# BatteryCharger.net
KiCad netlist of a schematic drawn in Altium Designer
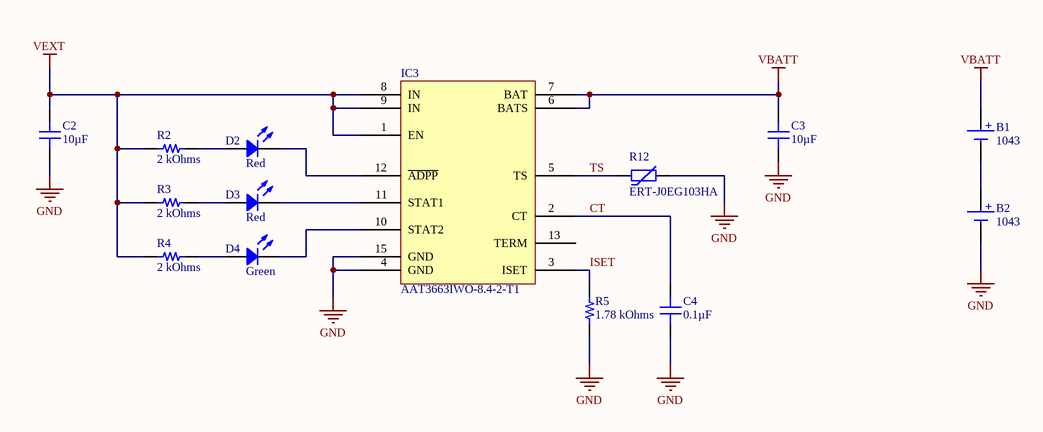
[diagram p0: BatteryCharger.SchDoc]

(export (version "E")
  (design (tool "Eeschema 10.0.6"))
  (components
    (comp (ref "B1")
      (value "1043")
      (footprint "KEYSTONE 1043")
      (description "BATTERY HOLDER 18650 PC PIN")
      (fields (field (name "MANUFACTURER") "Keystone Electronics"))
      (libsource (lib "Celestial Altium Library - altium_library") (part "Keystone 1043"))
    )
    (comp (ref "B2")
      (value "1043")
      (footprint "KEYSTONE 1043")
      (description "BATTERY HOLDER 18650 PC PIN")
      (fields (field (name "MANUFACTURER") "Keystone Electronics"))
      (libsource (lib "Celestial Altium Library - altium_library") (part "Keystone 1043"))
    )
    (comp (ref "C2")
      (value "10µF")
      (footprint "CAP 1206_3216 - 1.8MM")
      (description "CAP CER 10UF 10V X5R 1206")
      (fields
        (field (name "PART NUMBER") "CL31A106KPHNNNE")
        (field (name "MANUFACTURER") "Samsung Electro-Mechanics")
      )
      (libsource (lib "Celestial Altium Library - altium_library") (part "Capacitor"))
    )
    (comp (ref "C3")
      (value "10µF")
      (footprint "CAP 1206_3216 - 1.8MM")
      (description "CAP CER 10UF 10V X5R 1206")
      (fields
        (field (name "PART NUMBER") "CL31A106KPHNNNE")
        (field (name "MANUFACTURER") "Samsung Electro-Mechanics")
      )
      (libsource (lib "Celestial Altium Library - altium_library") (part "Capacitor"))
    )
    (comp (ref "C4")
      (value "0.1µF")
      (footprint "CAP 0603_1608")
      (description "CAP CER 0.1UF 25V Y5V 0603")
      (fields (field (name "PART NUMBER") "CC0603MRY5V8BB104") (field (name "MANUFACTURER") "Yageo"))
      (libsource (lib "Celestial Altium Library - altium_library") (part "Capacitor"))
    )
    (comp (ref "D2")
      (value "Red")
      (footprint "LED 0603_1608 RED")
      (description "LED RED CLEAR 2SMD")
      (fields
        (field (name "PART NUMBER") "19-213USRC/S259/TR8")
        (field (name "MANUFACTURER") "Everlight Electronics Co Ltd")
      )
      (libsource (lib "Celestial Altium Library - altium_library") (part "LED"))
    )
    (comp (ref "D3")
      (value "Red")
      (footprint "LED 0603_1608 RED")
      (description "LED RED CLEAR 2SMD")
      (fields
        (field (name "PART NUMBER") "19-213USRC/S259/TR8")
        (field (name "MANUFACTURER") "Everlight Electronics Co Ltd")
      )
      (libsource (lib "Celestial Altium Library - altium_library") (part "LED"))
    )
    (comp (ref "D4")
      (value "Green")
      (footprint "LED 0603_1608 GREEN")
      (description "LED GREEN CLEAR CHIP SMD")
      (fields (field (name "PART NUMBER") "LTST-C190KGKT") (field (name "MANUFACTURER") "Lite-On Inc."))
      (libsource (lib "Celestial Altium Library - altium_library") (part "LED"))
    )
    (comp (ref "IC3")
      (value "AAT3663IWO-8.4-2-T1")
      (footprint "SKYWORKS TDFN-14 3X3MM")
      (description "IC LI-ION CHARGER 14-DFN")
      (fields (field (name "MANUFACTURER") "Skyworks Solutions Inc."))
      (libsource (lib "Celestial Altium Library - altium_library") (part "SKYWORKS AAT3663"))
    )
    (comp (ref "R2")
      (value "2 kOhms")
      (footprint "RES 0603_1608")
      (description "RES SMD 2K OHM 5% 1/4W 0603")
      (fields
        (field (name "PART NUMBER") "ERJ-PA3J202V")
        (field (name "MANUFACTURER") "Panasonic Electronic Components")
      )
      (libsource (lib "Celestial Altium Library - altium_library") (part "Resistor"))
    )
    (comp (ref "R3")
      (value "2 kOhms")
      (footprint "RES 0603_1608")
      (description "RES SMD 2K OHM 5% 1/4W 0603")
      (fields
        (field (name "PART NUMBER") "ERJ-PA3J202V")
        (field (name "MANUFACTURER") "Panasonic Electronic Components")
      )
      (libsource (lib "Celestial Altium Library - altium_library") (part "Resistor"))
    )
    (comp (ref "R4")
      (value "2 kOhms")
      (footprint "RES 0603_1608")
      (description "RES SMD 2K OHM 5% 1/4W 0603")
      (fields
        (field (name "PART NUMBER") "ERJ-PA3J202V")
        (field (name "MANUFACTURER") "Panasonic Electronic Components")
      )
      (libsource (lib "Celestial Altium Library - altium_library") (part "Resistor"))
    )
    (comp (ref "R5")
      (value "1.78 kOhms")
      (footprint "RES 0603_1608")
      (description "RES SMD 1.78K OHM 1% 1/10W 0603")
      (fields
        (field (name "PART NUMBER") "ERJ-3EKF1781V")
        (field (name "MANUFACTURER") "Panasonic Electronic Components")
      )
      (libsource (lib "Celestial Altium Library - altium_library") (part "Resistor"))
    )
    (comp (ref "R12")
      (value "ERT-J0EG103HA")
      (footprint "NTC 0402_1005")
      (description "THERMISTOR NTC 10KOHM 3380K 0402")
      (fields (field (name "MANUFACTURER") "Panasonic Electronic Components"))
      (libsource (lib "Celestial Altium Library - altium_library") (part "Thermistor"))
    )
  )
  (nets
    (net (code "1") (name "/CT") (class "Default")
      (node (ref "C4") (pin "2") (pinfunction "2_2") (pintype "passive"))
      (node (ref "IC3") (pin "2") (pinfunction "CT_2") (pintype "passive"))
    )
    (net (code "2") (name "/ISET") (class "Default")
      (node (ref "IC3") (pin "3") (pinfunction "ISET_3") (pintype "passive"))
      (node (ref "R5") (pin "2") (pinfunction "2_2") (pintype "passive"))
    )
    (net (code "3") (name "/TS") (class "Default")
      (node (ref "IC3") (pin "5") (pinfunction "TS_5") (pintype "passive"))
      (node (ref "R12") (pin "1") (pinfunction "1_1") (pintype "passive"))
    )
    (net (code "4") (name "GND") (class "Default")
      (node (ref "B2") (pin "2") (pinfunction "-_2") (pintype "passive"))
      (node (ref "C2") (pin "1") (pinfunction "1_1") (pintype "passive"))
      (node (ref "C3") (pin "1") (pinfunction "1_1") (pintype "passive"))
      (node (ref "C4") (pin "1") (pinfunction "1_1") (pintype "passive"))
      (node (ref "IC3") (pin "15") (pinfunction "GND_15") (pintype "passive"))
      (node (ref "IC3") (pin "4") (pinfunction "GND_4") (pintype "passive"))
      (node (ref "R12") (pin "2") (pinfunction "2_2") (pintype "passive"))
      (node (ref "R5") (pin "1") (pinfunction "1_1") (pintype "passive"))
    )
    (net (code "5") (name "Net-(B1--)") (class "Default")
      (node (ref "B1") (pin "2") (pinfunction "-_2") (pintype "passive"))
      (node (ref "B2") (pin "1") (pinfunction "+_1") (pintype "passive"))
    )
    (net (code "6") (name "Net-(D2-Pad1)") (class "Default")
      (node (ref "D2") (pin "1") (pinfunction "1_1") (pintype "passive"))
      (node (ref "R2") (pin "2") (pinfunction "2_2") (pintype "passive"))
    )
    (net (code "7") (name "Net-(D3-Pad1)") (class "Default")
      (node (ref "D3") (pin "1") (pinfunction "1_1") (pintype "passive"))
      (node (ref "R3") (pin "2") (pinfunction "2_2") (pintype "passive"))
    )
    (net (code "8") (name "Net-(D4-Pad1)") (class "Default")
      (node (ref "D4") (pin "1") (pinfunction "1_1") (pintype "passive"))
      (node (ref "R4") (pin "2") (pinfunction "2_2") (pintype "passive"))
    )
    (net (code "9") (name "Net-(IC3-STAT1)") (class "Default")
      (node (ref "D3") (pin "2") (pinfunction "2_2") (pintype "passive"))
      (node (ref "IC3") (pin "11") (pinfunction "STAT1_11") (pintype "passive"))
    )
    (net (code "10") (name "Net-(IC3-STAT2)") (class "Default")
      (node (ref "D4") (pin "2") (pinfunction "2_2") (pintype "passive"))
      (node (ref "IC3") (pin "10") (pinfunction "STAT2_10") (pintype "passive"))
    )
    (net (code "11") (name "Net-(IC3-~{ADPP})") (class "Default")
      (node (ref "D2") (pin "2") (pinfunction "2_2") (pintype "passive"))
      (node (ref "IC3") (pin "12") (pinfunction "~{ADPP}_12") (pintype "passive"))
    )
    (net (code "12") (name "VBATT") (class "Default")
      (node (ref "B1") (pin "1") (pinfunction "+_1") (pintype "passive"))
      (node (ref "C3") (pin "2") (pinfunction "2_2") (pintype "passive"))
      (node (ref "IC3") (pin "6") (pinfunction "BATS_6") (pintype "passive"))
      (node (ref "IC3") (pin "7") (pinfunction "BAT_7") (pintype "passive"))
    )
    (net (code "13") (name "VEXT") (class "Default")
      (node (ref "C2") (pin "2") (pinfunction "2_2") (pintype "passive"))
      (node (ref "IC3") (pin "1") (pinfunction "EN_1") (pintype "passive"))
      (node (ref "IC3") (pin "8") (pinfunction "IN_8") (pintype "passive"))
      (node (ref "IC3") (pin "9") (pinfunction "IN_9") (pintype "passive"))
      (node (ref "R2") (pin "1") (pinfunction "1_1") (pintype "passive"))
      (node (ref "R3") (pin "1") (pinfunction "1_1") (pintype "passive"))
      (node (ref "R4") (pin "1") (pinfunction "1_1") (pintype "passive"))
    )
    (net (code "14") (name "unconnected-(IC3-TERM-Pad13)") (class "Default")
      (node (ref "IC3") (pin "13") (pinfunction "TERM_13") (pintype "passive"))
    )
  )
)
